# SprinklerBoard-8p.net
KiCad netlist of a schematic drawn in EAGLE
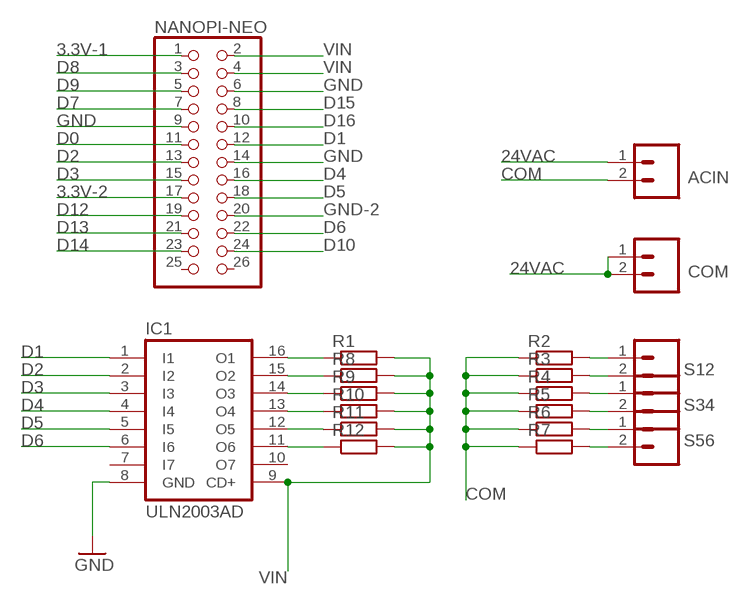
[diagram p0: schematic, sheet 1]

(export (version "E")
  (design (tool "Eeschema 10.0.6"))
  (components
    (comp (ref "ACIN")
      (value "M025MM-X")
      (footprint "eagle-import:SCREWTERMINAL-5MM-2-X")
      (libsource (lib "eagle-import") (part "M025MM-X"))
    )
    (comp (ref "COM")
      (value "M025MM-X")
      (footprint "eagle-import:SCREWTERMINAL-5MM-2-X")
      (libsource (lib "eagle-import") (part "M025MM-X"))
    )
    (comp (ref "IC1")
      (value "ULN2003AD")
      (footprint "eagle-import:SO16")
      (libsource (lib "eagle-import") (part "ULN2003AD"))
    )
    (comp (ref "NANOPI-NEO")
      (value "PINHD-2X13")
      (footprint "eagle-import:2X13")
      (libsource (lib "eagle-import") (part "PINHD-2X13"))
    )
    (comp (ref "R1")
      (value "R-EU_0204/5")
      (footprint "eagle-import:0204_5")
      (libsource (lib "eagle-import") (part "R-EU_0204/5"))
    )
    (comp (ref "R2")
      (value "R-EU_0207/15")
      (footprint "eagle-import:0207_15")
      (libsource (lib "eagle-import") (part "R-EU_0207/15"))
    )
    (comp (ref "R3")
      (value "R-EU_0207/15")
      (footprint "eagle-import:0207_15")
      (libsource (lib "eagle-import") (part "R-EU_0207/15"))
    )
    (comp (ref "R4")
      (value "R-EU_0207/15")
      (footprint "eagle-import:0207_15")
      (libsource (lib "eagle-import") (part "R-EU_0207/15"))
    )
    (comp (ref "R5")
      (value "R-EU_0207/15")
      (footprint "eagle-import:0207_15")
      (libsource (lib "eagle-import") (part "R-EU_0207/15"))
    )
    (comp (ref "R6")
      (value "R-EU_0207/15")
      (footprint "eagle-import:0207_15")
      (libsource (lib "eagle-import") (part "R-EU_0207/15"))
    )
    (comp (ref "R7")
      (value "R-EU_0207/15")
      (footprint "eagle-import:0207_15")
      (libsource (lib "eagle-import") (part "R-EU_0207/15"))
    )
    (comp (ref "R8")
      (value "R-EU_0204/5")
      (footprint "eagle-import:0204_5")
      (libsource (lib "eagle-import") (part "R-EU_0204/5"))
    )
    (comp (ref "R9")
      (value "R-EU_0204/5")
      (footprint "eagle-import:0204_5")
      (libsource (lib "eagle-import") (part "R-EU_0204/5"))
    )
    (comp (ref "R10")
      (value "R-EU_0204/5")
      (footprint "eagle-import:0204_5")
      (libsource (lib "eagle-import") (part "R-EU_0204/5"))
    )
    (comp (ref "R11")
      (value "R-EU_0204/5")
      (footprint "eagle-import:0204_5")
      (libsource (lib "eagle-import") (part "R-EU_0204/5"))
    )
    (comp (ref "R12")
      (value "R-EU_0204/5")
      (footprint "eagle-import:0204_5")
      (libsource (lib "eagle-import") (part "R-EU_0204/5"))
    )
    (comp (ref "S12")
      (value "M025MM-X")
      (footprint "eagle-import:SCREWTERMINAL-5MM-2-X")
      (libsource (lib "eagle-import") (part "M025MM-X"))
    )
    (comp (ref "S34")
      (value "M025MM-X")
      (footprint "eagle-import:SCREWTERMINAL-5MM-2-X")
      (libsource (lib "eagle-import") (part "M025MM-X"))
    )
    (comp (ref "S56")
      (value "M025MM-X")
      (footprint "eagle-import:SCREWTERMINAL-5MM-2-X")
      (libsource (lib "eagle-import") (part "M025MM-X"))
    )
  )
  (nets
    (net (code "1") (name "/3.3V-1") (class "Default")
      (node (ref "NANOPI-NEO") (pin "1") (pinfunction "1_1") (pintype "passive"))
    )
    (net (code "2") (name "/3.3V-2") (class "Default")
      (node (ref "NANOPI-NEO") (pin "17") (pinfunction "17_17") (pintype "passive"))
    )
    (net (code "3") (name "/24VAC") (class "Default")
      (node (ref "ACIN") (pin "1") (pinfunction "1_1") (pintype "passive"))
      (node (ref "COM") (pin "1") (pinfunction "1_1") (pintype "passive"))
      (node (ref "COM") (pin "2") (pinfunction "2_2") (pintype "passive"))
    )
    (net (code "4") (name "/COM") (class "Default")
      (node (ref "ACIN") (pin "2") (pinfunction "2_2") (pintype "passive"))
      (node (ref "R2") (pin "1") (pinfunction "1_1") (pintype "passive"))
      (node (ref "R3") (pin "1") (pinfunction "1_1") (pintype "passive"))
      (node (ref "R4") (pin "1") (pinfunction "1_1") (pintype "passive"))
      (node (ref "R5") (pin "1") (pinfunction "1_1") (pintype "passive"))
      (node (ref "R6") (pin "1") (pinfunction "1_1") (pintype "passive"))
      (node (ref "R7") (pin "1") (pinfunction "1_1") (pintype "passive"))
    )
    (net (code "5") (name "/D0") (class "Default")
      (node (ref "NANOPI-NEO") (pin "11") (pinfunction "11_11") (pintype "passive"))
    )
    (net (code "6") (name "/D1") (class "Default")
      (node (ref "IC1") (pin "1") (pinfunction "I1_1") (pintype "input"))
      (node (ref "NANOPI-NEO") (pin "12") (pinfunction "12_12") (pintype "passive"))
    )
    (net (code "7") (name "/D2") (class "Default")
      (node (ref "IC1") (pin "2") (pinfunction "I2_2") (pintype "input"))
      (node (ref "NANOPI-NEO") (pin "13") (pinfunction "13_13") (pintype "passive"))
    )
    (net (code "8") (name "/D3") (class "Default")
      (node (ref "IC1") (pin "3") (pinfunction "I3_3") (pintype "input"))
      (node (ref "NANOPI-NEO") (pin "15") (pinfunction "15_15") (pintype "passive"))
    )
    (net (code "9") (name "/D4") (class "Default")
      (node (ref "IC1") (pin "4") (pinfunction "I4_4") (pintype "input"))
      (node (ref "NANOPI-NEO") (pin "16") (pinfunction "16_16") (pintype "passive"))
    )
    (net (code "10") (name "/D5") (class "Default")
      (node (ref "IC1") (pin "5") (pinfunction "I5_5") (pintype "input"))
      (node (ref "NANOPI-NEO") (pin "18") (pinfunction "18_18") (pintype "passive"))
    )
    (net (code "11") (name "/D6") (class "Default")
      (node (ref "IC1") (pin "6") (pinfunction "I6_6") (pintype "input"))
      (node (ref "NANOPI-NEO") (pin "22") (pinfunction "22_22") (pintype "passive"))
    )
    (net (code "12") (name "/D7") (class "Default")
      (node (ref "NANOPI-NEO") (pin "7") (pinfunction "7_7") (pintype "passive"))
    )
    (net (code "13") (name "/D8") (class "Default")
      (node (ref "NANOPI-NEO") (pin "3") (pinfunction "3_3") (pintype "passive"))
    )
    (net (code "14") (name "/D9") (class "Default")
      (node (ref "NANOPI-NEO") (pin "5") (pinfunction "5_5") (pintype "passive"))
    )
    (net (code "15") (name "/D10") (class "Default")
      (node (ref "NANOPI-NEO") (pin "24") (pinfunction "24_24") (pintype "passive"))
    )
    (net (code "16") (name "/D12") (class "Default")
      (node (ref "NANOPI-NEO") (pin "19") (pinfunction "19_19") (pintype "passive"))
    )
    (net (code "17") (name "/D13") (class "Default")
      (node (ref "NANOPI-NEO") (pin "21") (pinfunction "21_21") (pintype "passive"))
    )
    (net (code "18") (name "/D14") (class "Default")
      (node (ref "NANOPI-NEO") (pin "23") (pinfunction "23_23") (pintype "passive"))
    )
    (net (code "19") (name "/D15") (class "Default")
      (node (ref "NANOPI-NEO") (pin "8") (pinfunction "8_8") (pintype "passive"))
    )
    (net (code "20") (name "/D16") (class "Default")
      (node (ref "NANOPI-NEO") (pin "10") (pinfunction "10_10") (pintype "passive"))
    )
    (net (code "21") (name "/GND-2") (class "Default")
      (node (ref "NANOPI-NEO") (pin "20") (pinfunction "20_20") (pintype "passive"))
    )
    (net (code "22") (name "/VIN") (class "Default")
      (node (ref "IC1") (pin "9") (pinfunction "CD+_9") (pintype "passive"))
      (node (ref "NANOPI-NEO") (pin "2") (pinfunction "2_2") (pintype "passive"))
      (node (ref "NANOPI-NEO") (pin "4") (pinfunction "4_4") (pintype "passive"))
      (node (ref "R1") (pin "2") (pinfunction "2_2") (pintype "passive"))
      (node (ref "R10") (pin "2") (pinfunction "2_2") (pintype "passive"))
      (node (ref "R11") (pin "2") (pinfunction "2_2") (pintype "passive"))
      (node (ref "R12") (pin "2") (pinfunction "2_2") (pintype "passive"))
      (node (ref "R8") (pin "2") (pinfunction "2_2") (pintype "passive"))
      (node (ref "R9") (pin "2") (pinfunction "2_2") (pintype "passive"))
    )
    (net (code "23") (name "GND") (class "Default")
      (node (ref "IC1") (pin "8") (pinfunction "GND_8") (pintype "power_in"))
      (node (ref "NANOPI-NEO") (pin "14") (pinfunction "14_14") (pintype "passive"))
      (node (ref "NANOPI-NEO") (pin "6") (pinfunction "6_6") (pintype "passive"))
      (node (ref "NANOPI-NEO") (pin "9") (pinfunction "9_9") (pintype "passive"))
    )
    (net (code "24") (name "Net-(IC1-O1)") (class "Default")
      (node (ref "IC1") (pin "16") (pinfunction "O1_16") (pintype "open_collector"))
      (node (ref "R1") (pin "1") (pinfunction "1_1") (pintype "passive"))
    )
    (net (code "25") (name "Net-(IC1-O2)") (class "Default")
      (node (ref "IC1") (pin "15") (pinfunction "O2_15") (pintype "open_collector"))
      (node (ref "R8") (pin "1") (pinfunction "1_1") (pintype "passive"))
    )
    (net (code "26") (name "Net-(IC1-O3)") (class "Default")
      (node (ref "IC1") (pin "14") (pinfunction "O3_14") (pintype "open_collector"))
      (node (ref "R9") (pin "1") (pinfunction "1_1") (pintype "passive"))
    )
    (net (code "27") (name "Net-(IC1-O4)") (class "Default")
      (node (ref "IC1") (pin "13") (pinfunction "O4_13") (pintype "open_collector"))
      (node (ref "R10") (pin "1") (pinfunction "1_1") (pintype "passive"))
    )
    (net (code "28") (name "Net-(IC1-O5)") (class "Default")
      (node (ref "IC1") (pin "12") (pinfunction "O5_12") (pintype "open_collector"))
      (node (ref "R11") (pin "1") (pinfunction "1_1") (pintype "passive"))
    )
    (net (code "29") (name "Net-(IC1-O6)") (class "Default")
      (node (ref "IC1") (pin "11") (pinfunction "O6_11") (pintype "open_collector"))
      (node (ref "R12") (pin "1") (pinfunction "1_1") (pintype "passive"))
    )
    (net (code "30") (name "Net-(R2-Pad2)") (class "Default")
      (node (ref "R2") (pin "2") (pinfunction "2_2") (pintype "passive"))
      (node (ref "S12") (pin "1") (pinfunction "1_1") (pintype "passive"))
    )
    (net (code "31") (name "Net-(R3-Pad2)") (class "Default")
      (node (ref "R3") (pin "2") (pinfunction "2_2") (pintype "passive"))
      (node (ref "S12") (pin "2") (pinfunction "2_2") (pintype "passive"))
    )
    (net (code "32") (name "Net-(R4-Pad2)") (class "Default")
      (node (ref "R4") (pin "2") (pinfunction "2_2") (pintype "passive"))
      (node (ref "S34") (pin "1") (pinfunction "1_1") (pintype "passive"))
    )
    (net (code "33") (name "Net-(R5-Pad2)") (class "Default")
      (node (ref "R5") (pin "2") (pinfunction "2_2") (pintype "passive"))
      (node (ref "S34") (pin "2") (pinfunction "2_2") (pintype "passive"))
    )
    (net (code "34") (name "Net-(R6-Pad2)") (class "Default")
      (node (ref "R6") (pin "2") (pinfunction "2_2") (pintype "passive"))
      (node (ref "S56") (pin "1") (pinfunction "1_1") (pintype "passive"))
    )
    (net (code "35") (name "Net-(R7-Pad2)") (class "Default")
      (node (ref "R7") (pin "2") (pinfunction "2_2") (pintype "passive"))
      (node (ref "S56") (pin "2") (pinfunction "2_2") (pintype "passive"))
    )
    (net (code "36") (name "unconnected-(IC1-I7-Pad7)") (class "Default")
      (node (ref "IC1") (pin "7") (pinfunction "I7_7") (pintype "input"))
    )
    (net (code "37") (name "unconnected-(IC1-O7-Pad10)") (class "Default")
      (node (ref "IC1") (pin "10") (pinfunction "O7_10") (pintype "open_collector"))
    )
    (net (code "38") (name "unconnected-(NANOPI-NEO-Pad25)") (class "Default")
      (node (ref "NANOPI-NEO") (pin "25") (pinfunction "25_25") (pintype "passive"))
    )
    (net (code "39") (name "unconnected-(NANOPI-NEO-Pad26)") (class "Default")
      (node (ref "NANOPI-NEO") (pin "26") (pinfunction "26_26") (pintype "passive"))
    )
  )
)
